# MCU.net
KiCad netlist of a schematic drawn in Altium Designer
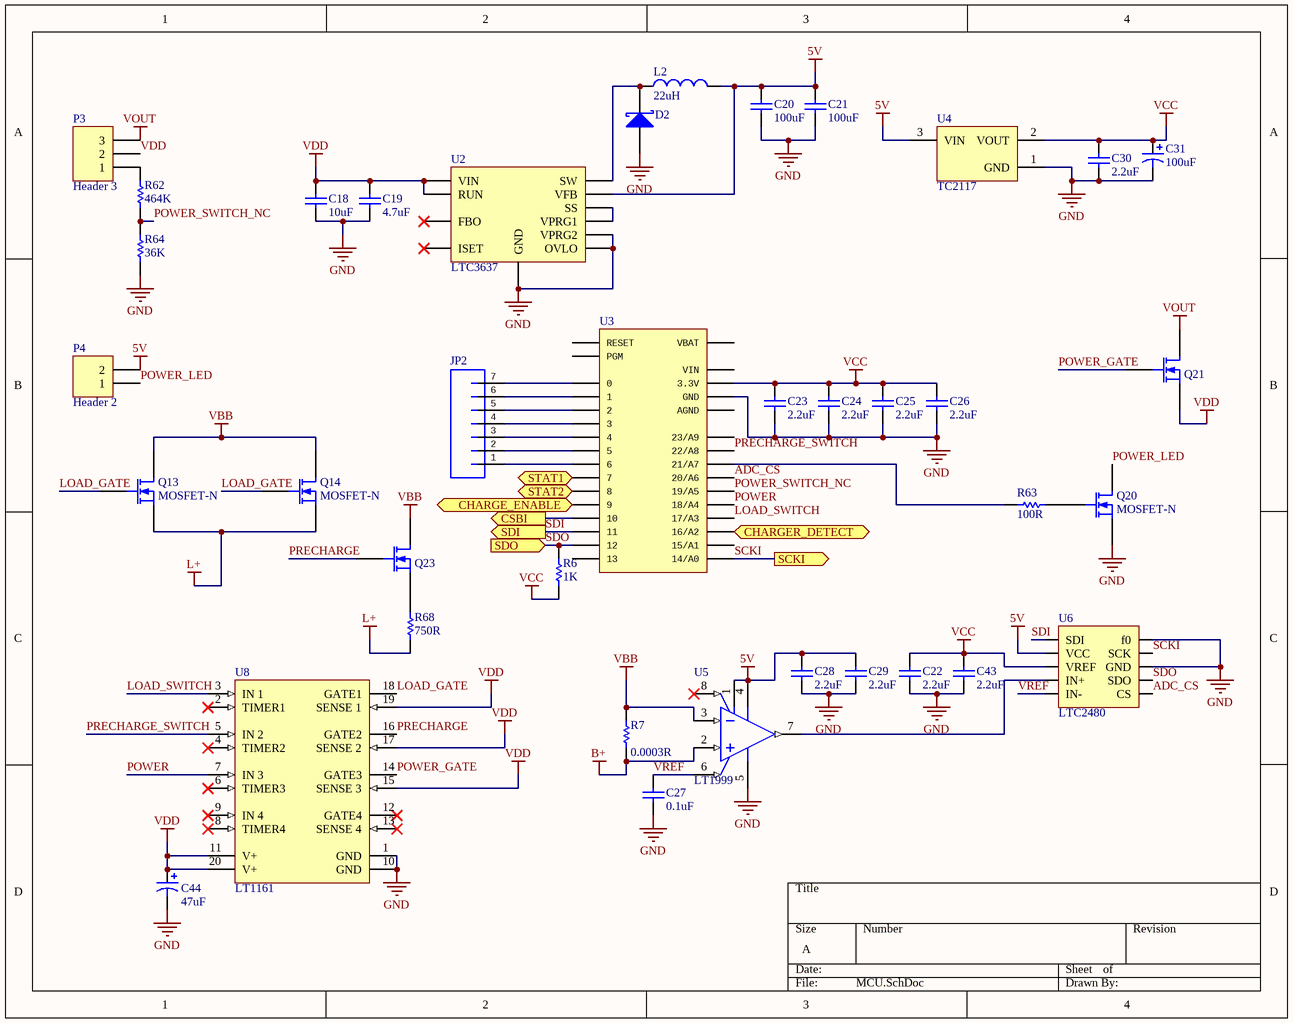
[diagram p0: MCU.SchDoc]

(export (version "E")
  (design (tool "Eeschema 10.0.6"))
  (components
    (comp (ref "C18")
      (value "10uF")
      (footprint "CAPC1206(3216)190_M")
      (description "CAP 10uF 50V Â±10% 1206 (3216 Metric) Thickness 1.9mm SMD")
      (fields (field (name "TOLERANCE") "Â±10%"))
      (libsource (lib "Altium Content Vault") (part "CMP-1037-04982-1"))
    )
    (comp (ref "C19")
      (value "4.7uF")
      (footprint "CAPC0805(2012)145_N")
      (description "CAP 4.7uF 50V Â±10% 0805 (2012 Metric) Thickness 1.45mm SMD")
      (fields (field (name "TOLERANCE") "Â±10%"))
      (libsource (lib "Altium Content Vault") (part "CMP-1036-04900-1"))
    )
    (comp (ref "C20")
      (value "100uF")
      (footprint "CAPC1210(3225)280_N")
      (description "CAP 100uF 10V Â±10% 1210 (3225 Metric) Thickness 2.8mm SMD")
      (fields (field (name "TOLERANCE") "Â±10%"))
      (libsource (lib "Altium Content Vault") (part "CMP-1038-02301-1"))
    )
    (comp (ref "C21")
      (value "100uF")
      (footprint "CAPC1210(3225)280_N")
      (description "CAP 100uF 10V Â±10% 1210 (3225 Metric) Thickness 2.8mm SMD")
      (fields (field (name "TOLERANCE") "Â±10%"))
      (libsource (lib "Altium Content Vault") (part "CMP-1038-02301-1"))
    )
    (comp (ref "C22")
      (value "2.2uF")
      (footprint "CAPC0603(1608)55_N")
      (description "CAP 2.2uF 4V Â±10% 0603 (1608 Metric) Thickness 0.55mm SMD")
      (fields (field (name "TOLERANCE") "Â±10%"))
      (libsource (lib "Altium Content Vault") (part "CMP-1035-02751-1"))
    )
    (comp (ref "C23")
      (value "2.2uF")
      (footprint "CAPC0603(1608)55_N")
      (description "CAP 2.2uF 16V Â±10% 0603 (1608 Metric) Thickness 0.55mm SMD")
      (fields (field (name "TOLERANCE") "Â±10%"))
      (libsource (lib "Altium Content Vault") (part "CMP-1035-02762-1"))
    )
    (comp (ref "C24")
      (value "2.2uF")
      (footprint "CAPC0603(1608)55_N")
      (description "CAP 2.2uF 16V Â±10% 0603 (1608 Metric) Thickness 0.55mm SMD")
      (fields (field (name "TOLERANCE") "Â±10%"))
      (libsource (lib "Altium Content Vault") (part "CMP-1035-02762-1"))
    )
    (comp (ref "C25")
      (value "2.2uF")
      (footprint "CAPC0603(1608)55_N")
      (description "CAP 2.2uF 16V Â±10% 0603 (1608 Metric) Thickness 0.55mm SMD")
      (fields (field (name "TOLERANCE") "Â±10%"))
      (libsource (lib "Altium Content Vault") (part "CMP-1035-02762-1"))
    )
    (comp (ref "C26")
      (value "2.2uF")
      (footprint "CAPC0603(1608)55_N")
      (description "CAP 2.2uF 16V Â±10% 0603 (1608 Metric) Thickness 0.55mm SMD")
      (fields (field (name "TOLERANCE") "Â±10%"))
      (libsource (lib "Altium Content Vault") (part "CMP-1035-02762-1"))
    )
    (comp (ref "C27")
      (value "0.1uF")
      (footprint "CAPC0603(1608)55_N")
      (description "CAP 2.2uF 16V Â±10% 0603 (1608 Metric) Thickness 0.55mm SMD")
      (fields (field (name "TOLERANCE") "Â±10%"))
      (libsource (lib "Altium Content Vault") (part "CMP-1035-02762-1"))
    )
    (comp (ref "C28")
      (value "2.2uF")
      (footprint "CAPC0603(1608)100_N")
      (description "CAP 100nF 6.3V Â±5% 0603 (1608 Metric) Thickness 1mm SMD")
      (fields (field (name "TOLERANCE") "Â±5%"))
      (libsource (lib "Altium Content Vault") (part "CMP-1035-02575-1"))
    )
    (comp (ref "C29")
      (value "2.2uF")
      (footprint "CAPC0603(1608)100_N")
      (description "CAP 1uF 6.3V Â±10% 0603 (1608 Metric) Thickness 1mm SMD")
      (fields (field (name "TOLERANCE") "Â±10%"))
      (libsource (lib "Altium Content Vault") (part "CMP-1035-02730-1"))
    )
    (comp (ref "C30")
      (value "2.2uF")
      (footprint "CAPC0603(1608)55_N")
      (description "CAP 2.2uF 16V Â±10% 0603 (1608 Metric) Thickness 0.55mm SMD")
      (fields (field (name "TOLERANCE") "Â±10%"))
      (libsource (lib "Altium Content Vault") (part "CMP-1035-02762-1"))
    )
    (comp (ref "C31")
      (value "100uF")
      (footprint "AVX-CAPC7343_V")
      (libsource (lib "Components") (part "AVX-CAP-P-2"))
    )
    (comp (ref "C43")
      (value "2.2uF")
      (footprint "CAPC0603(1608)55_N")
      (description "CAP 2.2uF 4V Â±10% 0603 (1608 Metric) Thickness 0.55mm SMD")
      (fields (field (name "TOLERANCE") "Â±10%"))
      (libsource (lib "Altium Content Vault") (part "CMP-1035-02751-1"))
    )
    (comp (ref "C44")
      (value "47uF")
      (footprint "CAP 300uF 6.3V")
      (description "Polarized Capacitor (Axial)")
      (fields (field (name "PUBLISHER") "Altium Limited"))
      (libsource (lib "Components") (part "CAP 47uF 50V"))
    )
    (comp (ref "D2")
      (value "~")
      (footprint "SMB")
      (description "Schottky Diode")
      (fields (field (name "PUBLISHER") "Altium Limited"))
      (libsource (lib "Miscellaneous Devices") (part "D Schottky"))
    )
    (comp (ref "JP2") (value "~") (footprint "JST-7-PTH") (libsource (lib "Components") (part "JST_7_RIGHT")))
    (comp (ref "L2")
      (value "22uH")
      (footprint "SDR0805-180ML")
      (description "Inductor")
      (fields (field (name "Comment") "SDR0805-180ML") (field (name "PUBLISHER") "Altium Limited"))
      (libsource (lib "Components") (part "SDR0805-180ML"))
    )
    (comp (ref "P3")
      (value "Header 3")
      (footprint "HDR1X3")
      (description "Header, 3-Pin")
      (fields (field (name "PUBLISHER") "Altium Limited"))
      (libsource (lib "Miscellaneous Connectors") (part "Header 3"))
    )
    (comp (ref "P4")
      (value "Header 2")
      (footprint "HDR1X2")
      (description "Header, 2-Pin")
      (fields (field (name "PUBLISHER") "Altium Limited"))
      (libsource (lib "Miscellaneous Connectors") (part "Header 2"))
    )
    (comp (ref "Q13")
      (value "MOSFET-N")
      (footprint "DPAK127P1525X483-7N")
      (description "N-Channel MOSFET")
      (fields (field (name "PUBLISHER") "Altium Limited"))
      (libsource (lib "Components") (part "MOSFET-N"))
    )
    (comp (ref "Q14")
      (value "MOSFET-N")
      (footprint "DPAK127P1525X483-7N")
      (description "N-Channel MOSFET")
      (fields (field (name "PUBLISHER") "Altium Limited"))
      (libsource (lib "Components") (part "MOSFET-N"))
    )
    (comp (ref "Q20")
      (value "MOSFET-N")
      (footprint "SOT23-3")
      (description "N-Channel MOSFET")
      (fields (field (name "PUBLISHER") "Altium Limited"))
      (libsource (lib "Components") (part "MOSFET-N"))
    )
    (comp (ref "Q21")
      (value "MOSFET-N")
      (footprint "SOIC127P600X175-8N")
      (description "N-Channel MOSFET")
      (fields (field (name "PUBLISHER") "Altium Limited"))
      (libsource (lib "Components") (part "MOSFET-N"))
    )
    (comp (ref "Q23")
      (value "MOSFET-N")
      (footprint "SOT23-3")
      (description "N-Channel MOSFET")
      (fields (field (name "PUBLISHER") "Altium Limited"))
      (libsource (lib "Components") (part "MOSFET-N"))
    )
    (comp (ref "R6")
      (value "1K")
      (footprint "RESC0603(1608)_L")
      (description "1K 0.1W 5% 0603 (1608 Metric)  SMD")
      (fields (field (name "TOLERANCE") "5 %") (field (name "POWER") "0.1 W"))
      (libsource (lib "Altium Content Vault") (part "RES"))
    )
    (comp (ref "R7")
      (value "0.0003R")
      (footprint "WSLP5931")
      (description "Resistor")
      (fields (field (name "PUBLISHER") "Altium Limited"))
      (libsource (lib "Components") (part "SHUNT"))
    )
    (comp (ref "R62")
      (value "464K")
      (footprint "RESC0603(1608)_M")
      (description "464K 0.1W 1% 0603 (1608 Metric)  SMD")
      (fields (field (name "TOLERANCE") "1 %") (field (name "POWER") "0.1 W"))
      (libsource (lib "Altium Content Vault") (part "RES"))
    )
    (comp (ref "R63")
      (value "100R")
      (footprint "RESC0603(1608)_L")
      (description "100R 0.1W 5% 0603 (1608 Metric)  SMD")
      (fields (field (name "TOLERANCE") "5 %") (field (name "POWER") "0.1 W"))
      (libsource (lib "Altium Content Vault") (part "RES"))
    )
    (comp (ref "R64")
      (value "36K")
      (footprint "RESC0603(1608)_M")
      (description "36K 0.1W 1% 0603 (1608 Metric)  SMD")
      (fields (field (name "POWER") "0.1 W") (field (name "TOLERANCE") "1 %"))
      (libsource (lib "Altium Content Vault") (part "RES"))
    )
    (comp (ref "R68")
      (value "750R")
      (footprint "RESC2512(6432)_N")
      (description "750R 1W 1% 2512 (6432 Metric)  SMD")
      (fields (field (name "TOLERANCE") "1 %") (field (name "POWER") "1 W"))
      (libsource (lib "Altium Content Vault") (part "RES"))
    )
    (comp (ref "U2")
      (value "LTC3637")
      (footprint "SON50P300X85_HS-17N")
      (libsource (lib "Components") (part "LTC3637"))
    )
    (comp (ref "U3")
      (value "~")
      (footprint "TEENSY_3.0_BASIC")
      (libsource (lib "Components") (part "TEENSY_3.0_BASIC"))
    )
    (comp (ref "U4")
      (value "TC2117")
      (footprint "SOT-223-DB3_M")
      (libsource (lib "Components") (part "PM-LINEREG-TC2117-IL4"))
    )
    (comp (ref "U5")
      (value "LT1999")
      (footprint "LT-MS8-8_N")
      (fields
        (field (name "MANUFACTURER") "Linear Technology")
        (field (name "PARTNUMBER") "LT1999HMS8-20#TRPBF")
        (field (name "LINEAR TECHNOLOGY PART NUMBER") "LT1999-20")
      )
      (libsource (lib "Altium Content Vault") (part "CMP-0359-00619-2"))
    )
    (comp (ref "U6") (value "LTC2480") (footprint "MSOP10") (libsource (lib "Components") (part "LTC2480")))
    (comp (ref "U8")
      (value "LT1161")
      (footprint "LT-SW-20_M")
      (fields (field (name "MANUFACTURER") "Linear Technology") (field (name "PARTNUMBER") "LT1161ISW#PBF"))
      (libsource (lib "Altium Inc") (part "LT-LT1161-20"))
    )
  )
  (nets
    (net (code "1") (name "/ADC_CS") (class "Default")
      (node (ref "U3") (pin "20/A6") (pinfunction "20/A6_20/A6") (pintype "passive"))
      (node (ref "U6") (pin "9") (pinfunction "CS_9") (pintype "passive"))
    )
    (net (code "2") (name "/CHARGER_DETECT") (class "Default")
      (node (ref "U3") (pin "16/A2") (pinfunction "16/A2_16/A2") (pintype "passive"))
    )
    (net (code "3") (name "/CHARGE_ENABLE") (class "Default")
      (node (ref "U3") (pin "9") (pinfunction "9_9") (pintype "passive"))
    )
    (net (code "4") (name "/CSBI") (class "Default")
      (node (ref "U3") (pin "10") (pinfunction "10_10") (pintype "passive"))
    )
    (net (code "5") (name "/LOAD_GATE") (class "Default")
      (node (ref "Q13") (pin "1") (pinfunction "G_1") (pintype "passive"))
      (node (ref "Q14") (pin "1") (pinfunction "G_1") (pintype "passive"))
      (node (ref "U8") (pin "18") (pinfunction "GATE1_18") (pintype "tri_state"))
    )
    (net (code "6") (name "/LOAD_SWITCH") (class "Default")
      (node (ref "U3") (pin "17/A3") (pinfunction "17/A3_17/A3") (pintype "passive"))
      (node (ref "U8") (pin "3") (pinfunction "IN_1_3") (pintype "input"))
    )
    (net (code "7") (name "/POWER") (class "Default")
      (node (ref "U3") (pin "18/A4") (pinfunction "18/A4_18/A4") (pintype "passive"))
      (node (ref "U8") (pin "7") (pinfunction "IN_3_7") (pintype "input"))
    )
    (net (code "8") (name "/POWER_GATE") (class "Default")
      (node (ref "Q21") (pin "1") (pinfunction "G_1") (pintype "passive"))
      (node (ref "U8") (pin "14") (pinfunction "GATE3_14") (pintype "tri_state"))
    )
    (net (code "9") (name "/POWER_LED") (class "Default")
      (node (ref "P4") (pin "1") (pinfunction "1_1") (pintype "passive"))
      (node (ref "Q20") (pin "2") (pinfunction "D_2") (pintype "passive"))
    )
    (net (code "10") (name "/POWER_SWITCH_NC") (class "Default")
      (node (ref "R62") (pin "1") (pinfunction "1_1") (pintype "passive"))
      (node (ref "R64") (pin "2") (pinfunction "2_2") (pintype "passive"))
      (node (ref "U3") (pin "19/A5") (pinfunction "19/A5_19/A5") (pintype "passive"))
    )
    (net (code "11") (name "/PRECHARGE") (class "Default")
      (node (ref "Q23") (pin "1") (pinfunction "G_1") (pintype "passive"))
      (node (ref "U8") (pin "16") (pinfunction "GATE2_16") (pintype "tri_state"))
    )
    (net (code "12") (name "/PRECHARGE_SWITCH") (class "Default")
      (node (ref "U3") (pin "22/A8") (pinfunction "22/A8_22/A8") (pintype "passive"))
      (node (ref "U8") (pin "5") (pinfunction "IN_2_5") (pintype "input"))
    )
    (net (code "13") (name "/SCKI") (class "Default")
      (node (ref "U3") (pin "14/A0") (pinfunction "14/A0_14/A0") (pintype "passive"))
      (node (ref "U6") (pin "6") (pinfunction "SCK_6") (pintype "passive"))
    )
    (net (code "14") (name "/SDI") (class "Default")
      (node (ref "U3") (pin "11") (pinfunction "11_11") (pintype "passive"))
      (node (ref "U6") (pin "0") (pinfunction "SDI_0") (pintype "passive"))
    )
    (net (code "15") (name "/SDO") (class "Default")
      (node (ref "R6") (pin "2") (pinfunction "2_2") (pintype "passive"))
      (node (ref "U3") (pin "12") (pinfunction "12_12") (pintype "passive"))
      (node (ref "U6") (pin "8") (pinfunction "SDO_8") (pintype "passive"))
    )
    (net (code "16") (name "/STAT1") (class "Default")
      (node (ref "U3") (pin "7") (pinfunction "7_7") (pintype "passive"))
    )
    (net (code "17") (name "/STAT2") (class "Default")
      (node (ref "U3") (pin "8") (pinfunction "8_8") (pintype "passive"))
    )
    (net (code "18") (name "/VREF") (class "Default")
      (node (ref "C27") (pin "2") (pinfunction "2_2") (pintype "passive"))
      (node (ref "U5") (pin "6") (pinfunction "REF_6") (pintype "input"))
      (node (ref "U6") (pin "4") (pinfunction "IN-_4") (pintype "passive"))
    )
    (net (code "19") (name "5V") (class "Default")
      (node (ref "C20") (pin "2") (pinfunction "2_2") (pintype "passive"))
      (node (ref "C21") (pin "2") (pinfunction "2_2") (pintype "passive"))
      (node (ref "C28") (pin "2") (pinfunction "2_2") (pintype "passive"))
      (node (ref "C29") (pin "2") (pinfunction "2_2") (pintype "passive"))
      (node (ref "L2") (pin "2") (pinfunction "2_2") (pintype "passive"))
      (node (ref "P4") (pin "2") (pinfunction "2_2") (pintype "passive"))
      (node (ref "U2") (pin "9") (pinfunction "VFB_9") (pintype "passive"))
      (node (ref "U4") (pin "3") (pinfunction "VIN_3") (pintype "power_in"))
      (node (ref "U5") (pin "1") (pinfunction "V+_1") (pintype "power_in"))
      (node (ref "U5") (pin "4") (pinfunction "V+_4") (pintype "power_in"))
      (node (ref "U6") (pin "1") (pinfunction "VCC_1") (pintype "passive"))
    )
    (net (code "20") (name "B+") (class "Default")
      (node (ref "R7") (pin "2") (pinfunction "2_2") (pintype "passive"))
      (node (ref "U5") (pin "2") (pinfunction "+IN_2") (pintype "input"))
    )
    (net (code "21") (name "GND") (class "Default")
      (node (ref "C18") (pin "1") (pinfunction "1_1") (pintype "passive"))
      (node (ref "C19") (pin "2") (pinfunction "2_2") (pintype "passive"))
      (node (ref "C20") (pin "1") (pinfunction "1_1") (pintype "passive"))
      (node (ref "C21") (pin "1") (pinfunction "1_1") (pintype "passive"))
      (node (ref "C22") (pin "1") (pinfunction "1_1") (pintype "passive"))
      (node (ref "C23") (pin "1") (pinfunction "1_1") (pintype "passive"))
      (node (ref "C24") (pin "1") (pinfunction "1_1") (pintype "passive"))
      (node (ref "C25") (pin "1") (pinfunction "1_1") (pintype "passive"))
      (node (ref "C26") (pin "1") (pinfunction "1_1") (pintype "passive"))
      (node (ref "C27") (pin "1") (pinfunction "1_1") (pintype "passive"))
      (node (ref "C28") (pin "1") (pinfunction "1_1") (pintype "passive"))
      (node (ref "C29") (pin "1") (pinfunction "1_1") (pintype "passive"))
      (node (ref "C30") (pin "2") (pinfunction "2_2") (pintype "passive"))
      (node (ref "C31") (pin "2") (pinfunction "2_2") (pintype "passive"))
      (node (ref "C43") (pin "1") (pinfunction "1_1") (pintype "passive"))
      (node (ref "C44") (pin "2") (pinfunction "2_2") (pintype "passive"))
      (node (ref "D2") (pin "1") (pinfunction "A_1") (pintype "passive"))
      (node (ref "Q20") (pin "3") (pinfunction "S_3") (pintype "passive"))
      (node (ref "R64") (pin "1") (pinfunction "1_1") (pintype "passive"))
      (node (ref "U2") (pin "12") (pinfunction "OVLO_12") (pintype "passive"))
      (node (ref "U2") (pin "17") (pinfunction "GND_17") (pintype "passive"))
      (node (ref "U2") (pin "6") (pinfunction "VPRG2_6") (pintype "passive"))
      (node (ref "U3") (pin "GND_GND1") (pinfunction "GND_GND_GND1") (pintype "power_in"))
      (node (ref "U4") (pin "1") (pinfunction "GND_1") (pintype "power_in"))
      (node (ref "U5") (pin "5") (pinfunction "GND_5") (pintype "power_in"))
      (node (ref "U6") (pin "5") (pinfunction "f0_5") (pintype "passive"))
      (node (ref "U6") (pin "7") (pinfunction "GND_7") (pintype "passive"))
      (node (ref "U8") (pin "1") (pinfunction "GND_1") (pintype "power_in"))
      (node (ref "U8") (pin "10") (pinfunction "GND_10") (pintype "power_in"))
    )
    (net (code "22") (name "L+") (class "Default")
      (node (ref "Q13") (pin "3") (pinfunction "S_3") (pintype "passive"))
      (node (ref "Q14") (pin "3") (pinfunction "S_3") (pintype "passive"))
      (node (ref "R68") (pin "1") (pinfunction "1_1") (pintype "passive"))
    )
    (net (code "23") (name "Net-(D2-K)") (class "Default")
      (node (ref "D2") (pin "2") (pinfunction "K_2") (pintype "passive"))
      (node (ref "L2") (pin "1") (pinfunction "1_1") (pintype "passive"))
      (node (ref "U2") (pin "1") (pinfunction "SW_1") (pintype "passive"))
    )
    (net (code "24") (name "Net-(JP2-Pad1)") (class "Default")
      (node (ref "JP2") (pin "1") (pinfunction "1_1") (pintype "passive"))
      (node (ref "U3") (pin "6") (pinfunction "6_6") (pintype "passive"))
    )
    (net (code "25") (name "Net-(JP2-Pad2)") (class "Default")
      (node (ref "JP2") (pin "2") (pinfunction "2_2") (pintype "passive"))
      (node (ref "U3") (pin "5") (pinfunction "5_5") (pintype "passive"))
    )
    (net (code "26") (name "Net-(JP2-Pad3)") (class "Default")
      (node (ref "JP2") (pin "3") (pinfunction "3_3") (pintype "passive"))
      (node (ref "U3") (pin "4") (pinfunction "4_4") (pintype "passive"))
    )
    (net (code "27") (name "Net-(JP2-Pad4)") (class "Default")
      (node (ref "JP2") (pin "4") (pinfunction "4_4") (pintype "passive"))
      (node (ref "U3") (pin "3") (pinfunction "3_3") (pintype "passive"))
    )
    (net (code "28") (name "Net-(JP2-Pad5)") (class "Default")
      (node (ref "JP2") (pin "5") (pinfunction "5_5") (pintype "passive"))
      (node (ref "U3") (pin "2") (pinfunction "2_2") (pintype "passive"))
    )
    (net (code "29") (name "Net-(JP2-Pad6)") (class "Default")
      (node (ref "JP2") (pin "6") (pinfunction "6_6") (pintype "passive"))
      (node (ref "U3") (pin "1") (pinfunction "1_1") (pintype "passive"))
    )
    (net (code "30") (name "Net-(JP2-Pad7)") (class "Default")
      (node (ref "JP2") (pin "7") (pinfunction "7_7") (pintype "passive"))
      (node (ref "U3") (pin "0") (pinfunction "0_0") (pintype "passive"))
    )
    (net (code "31") (name "Net-(P3-Pad1)") (class "Default")
      (node (ref "P3") (pin "1") (pinfunction "1_1") (pintype "passive"))
      (node (ref "R62") (pin "2") (pinfunction "2_2") (pintype "passive"))
    )
    (net (code "32") (name "Net-(Q20-G)") (class "Default")
      (node (ref "Q20") (pin "1") (pinfunction "G_1") (pintype "passive"))
      (node (ref "R63") (pin "2") (pinfunction "2_2") (pintype "passive"))
    )
    (net (code "33") (name "Net-(Q23-S)") (class "Default")
      (node (ref "Q23") (pin "3") (pinfunction "S_3") (pintype "passive"))
      (node (ref "R68") (pin "2") (pinfunction "2_2") (pintype "passive"))
    )
    (net (code "34") (name "Net-(R63-Pad1)") (class "Default")
      (node (ref "R63") (pin "1") (pinfunction "1_1") (pintype "passive"))
      (node (ref "U3") (pin "21/A7") (pinfunction "21/A7_21/A7") (pintype "passive"))
    )
    (net (code "35") (name "Net-(U2-SS)") (class "Default")
      (node (ref "U2") (pin "10") (pinfunction "SS_10") (pintype "passive"))
      (node (ref "U2") (pin "7") (pinfunction "VPRG1_7") (pintype "passive"))
    )
    (net (code "36") (name "Net-(U5-OUT)") (class "Default")
      (node (ref "U5") (pin "7") (pinfunction "OUT_7") (pintype "output"))
      (node (ref "U6") (pin "3") (pinfunction "IN+_3") (pintype "passive"))
    )
    (net (code "37") (name "VBB") (class "Default")
      (node (ref "Q13") (pin "2") (pinfunction "D_2") (pintype "passive"))
      (node (ref "Q14") (pin "2") (pinfunction "D_2") (pintype "passive"))
      (node (ref "Q23") (pin "2") (pinfunction "D_2") (pintype "passive"))
      (node (ref "R7") (pin "1") (pinfunction "1_1") (pintype "passive"))
      (node (ref "U5") (pin "3") (pinfunction "-IN_3") (pintype "input"))
    )
    (net (code "38") (name "VCC") (class "Default")
      (node (ref "C22") (pin "2") (pinfunction "2_2") (pintype "passive"))
      (node (ref "C23") (pin "2") (pinfunction "2_2") (pintype "passive"))
      (node (ref "C24") (pin "2") (pinfunction "2_2") (pintype "passive"))
      (node (ref "C25") (pin "2") (pinfunction "2_2") (pintype "passive"))
      (node (ref "C26") (pin "2") (pinfunction "2_2") (pintype "passive"))
      (node (ref "C30") (pin "1") (pinfunction "1_1") (pintype "passive"))
      (node (ref "C31") (pin "1") (pinfunction "1_1") (pintype "passive"))
      (node (ref "C43") (pin "2") (pinfunction "2_2") (pintype "passive"))
      (node (ref "R6") (pin "1") (pinfunction "1_1") (pintype "passive"))
      (node (ref "U3") (pin "3.3V_3.3V1") (pinfunction "3.3V_3.3V_3.3V1") (pintype "power_in"))
      (node (ref "U4") (pin "2") (pinfunction "VOUT_2") (pintype "power_in"))
      (node (ref "U6") (pin "2") (pinfunction "VREF_2") (pintype "passive"))
    )
    (net (code "39") (name "VDD") (class "Default")
      (node (ref "C18") (pin "2") (pinfunction "2_2") (pintype "passive"))
      (node (ref "C19") (pin "1") (pinfunction "1_1") (pintype "passive"))
      (node (ref "C44") (pin "1") (pinfunction "1_1") (pintype "passive"))
      (node (ref "P3") (pin "2") (pinfunction "2_2") (pintype "passive"))
      (node (ref "Q21") (pin "3") (pinfunction "S_3") (pintype "passive"))
      (node (ref "U2") (pin "14") (pinfunction "RUN_14") (pintype "passive"))
      (node (ref "U2") (pin "3") (pinfunction "VIN_3") (pintype "passive"))
      (node (ref "U8") (pin "11") (pinfunction "V+_11") (pintype "power_in"))
      (node (ref "U8") (pin "15") (pinfunction "SENSE_3_15") (pintype "input"))
      (node (ref "U8") (pin "17") (pinfunction "SENSE_2_17") (pintype "input"))
      (node (ref "U8") (pin "19") (pinfunction "SENSE_1_19") (pintype "input"))
      (node (ref "U8") (pin "20") (pinfunction "V+_20") (pintype "power_in"))
    )
    (net (code "40") (name "VOUT") (class "Default")
      (node (ref "P3") (pin "3") (pinfunction "3_3") (pintype "passive"))
      (node (ref "Q21") (pin "2") (pinfunction "D_2") (pintype "passive"))
    )
    (net (code "41") (name "unconnected-(U2-FBO-Pad5)") (class "Default")
      (node (ref "U2") (pin "5") (pinfunction "FBO_5") (pintype "passive+no_connect"))
    )
    (net (code "42") (name "unconnected-(U2-ISET-Pad11)") (class "Default")
      (node (ref "U2") (pin "11") (pinfunction "ISET_11") (pintype "passive+no_connect"))
    )
    (net (code "43") (name "unconnected-(U3-Pad13)") (class "Default")
      (node (ref "U3") (pin "13") (pinfunction "13_13") (pintype "passive"))
    )
    (net (code "44") (name "unconnected-(U3-Pad15{slash}A1)") (class "Default")
      (node (ref "U3") (pin "15/A1") (pinfunction "15/A1_15/A1") (pintype "passive"))
    )
    (net (code "45") (name "unconnected-(U3-Pad23{slash}A9)") (class "Default")
      (node (ref "U3") (pin "23/A9") (pinfunction "23/A9_23/A9") (pintype "passive"))
    )
    (net (code "46") (name "unconnected-(U3-PadAGND)") (class "Default")
      (node (ref "U3") (pin "AGND") (pinfunction "AGND_AGND") (pintype "power_in"))
    )
    (net (code "47") (name "unconnected-(U3-PadPGM)") (class "Default")
      (node (ref "U3") (pin "PGM") (pinfunction "PGM_PGM") (pintype "passive"))
    )
    (net (code "48") (name "unconnected-(U3-PadRESET)") (class "Default")
      (node (ref "U3") (pin "RESET") (pinfunction "RESET_RESET") (pintype "passive"))
    )
    (net (code "49") (name "unconnected-(U3-PadVBAT)") (class "Default")
      (node (ref "U3") (pin "VBAT") (pinfunction "VBAT_VBAT") (pintype "power_in"))
    )
    (net (code "50") (name "unconnected-(U3-PadVIN)") (class "Default")
      (node (ref "U3") (pin "VIN") (pinfunction "VIN_VIN") (pintype "power_in"))
    )
    (net (code "51") (name "unconnected-(U5-~{SHDN}-Pad8)") (class "Default")
      (node (ref "U5") (pin "8") (pinfunction "~{SHDN}_8") (pintype "input+no_connect"))
    )
    (net (code "52") (name "unconnected-(U8-GATE4-Pad12)") (class "Default")
      (node (ref "U8") (pin "12") (pinfunction "GATE4_12") (pintype "tri_state+no_connect"))
    )
    (net (code "53") (name "unconnected-(U8-IN_4-Pad9)") (class "Default")
      (node (ref "U8") (pin "9") (pinfunction "IN_4_9") (pintype "input+no_connect"))
    )
    (net (code "54") (name "unconnected-(U8-SENSE_4-Pad13)") (class "Default")
      (node (ref "U8") (pin "13") (pinfunction "SENSE_4_13") (pintype "input+no_connect"))
    )
    (net (code "55") (name "unconnected-(U8-TIMER1-Pad2)") (class "Default")
      (node (ref "U8") (pin "2") (pinfunction "TIMER1_2") (pintype "input+no_connect"))
    )
    (net (code "56") (name "unconnected-(U8-TIMER2-Pad4)") (class "Default")
      (node (ref "U8") (pin "4") (pinfunction "TIMER2_4") (pintype "input+no_connect"))
    )
    (net (code "57") (name "unconnected-(U8-TIMER3-Pad6)") (class "Default")
      (node (ref "U8") (pin "6") (pinfunction "TIMER3_6") (pintype "input+no_connect"))
    )
    (net (code "58") (name "unconnected-(U8-TIMER4-Pad8)") (class "Default")
      (node (ref "U8") (pin "8") (pinfunction "TIMER4_8") (pintype "input+no_connect"))
    )
  )
)
